# main-pcb_aveon.net
KiCad netlist of a schematic drawn in EAGLE
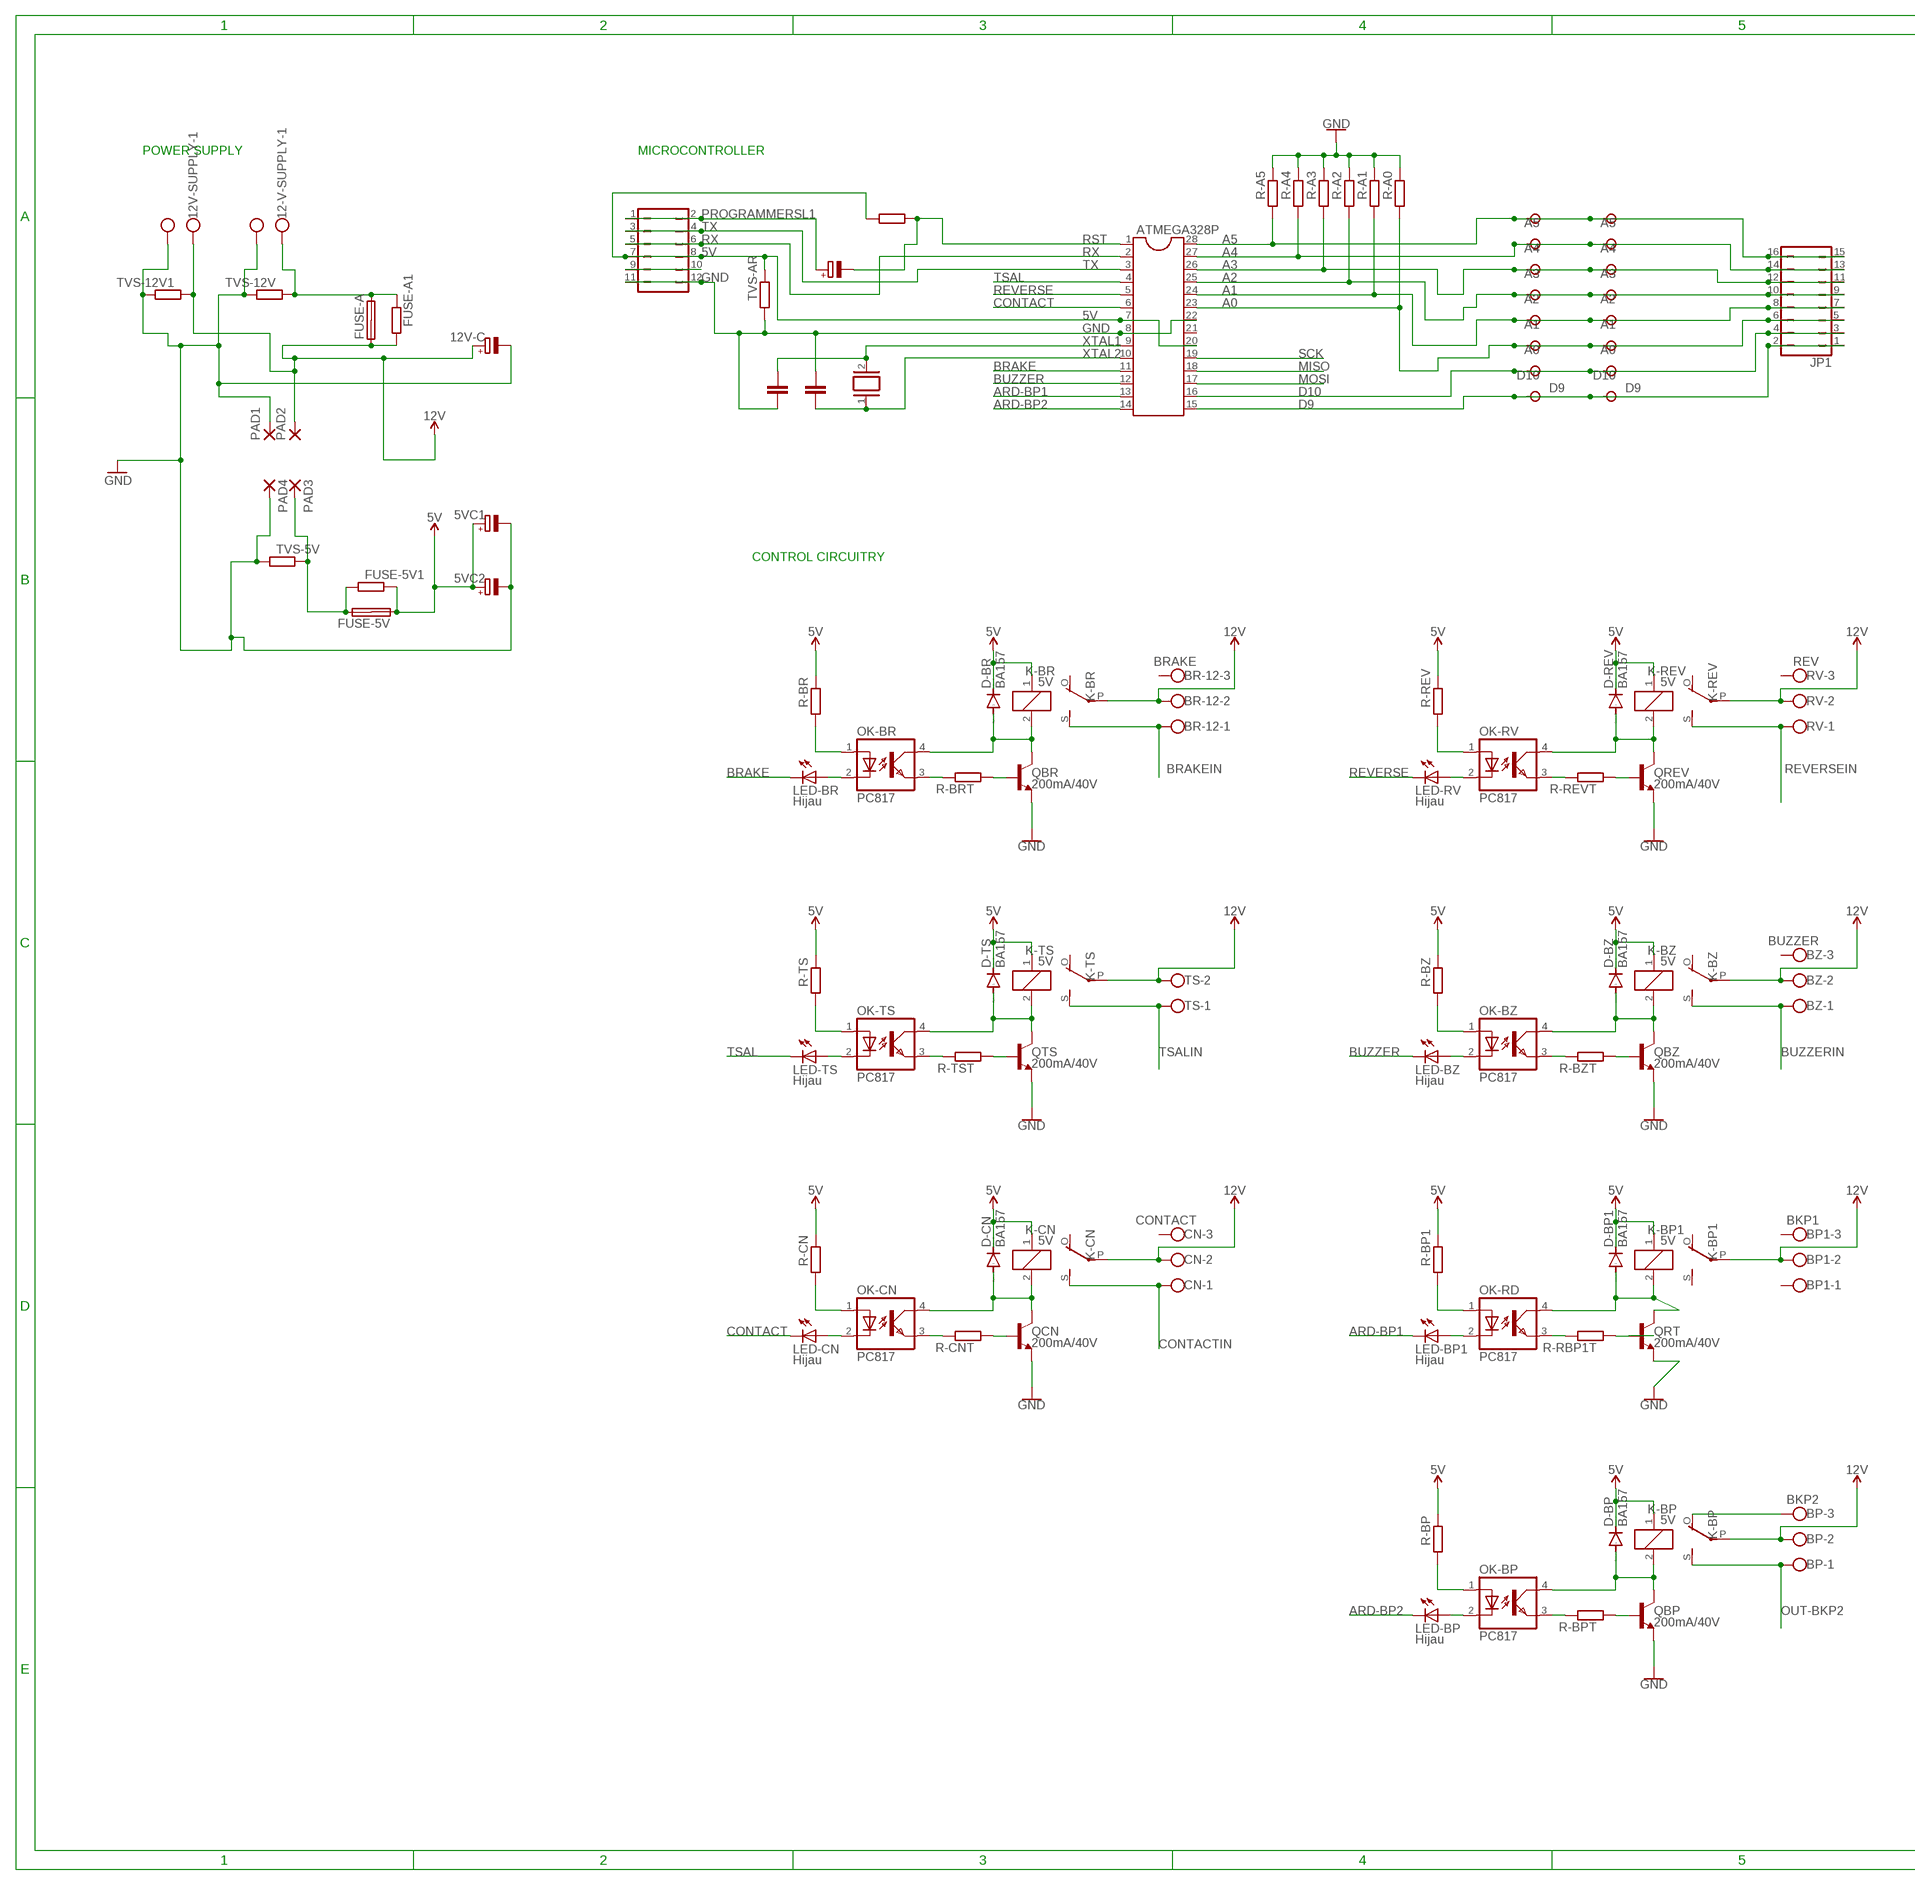
[diagram p0: schematic, sheet 1, part 1 of 2]
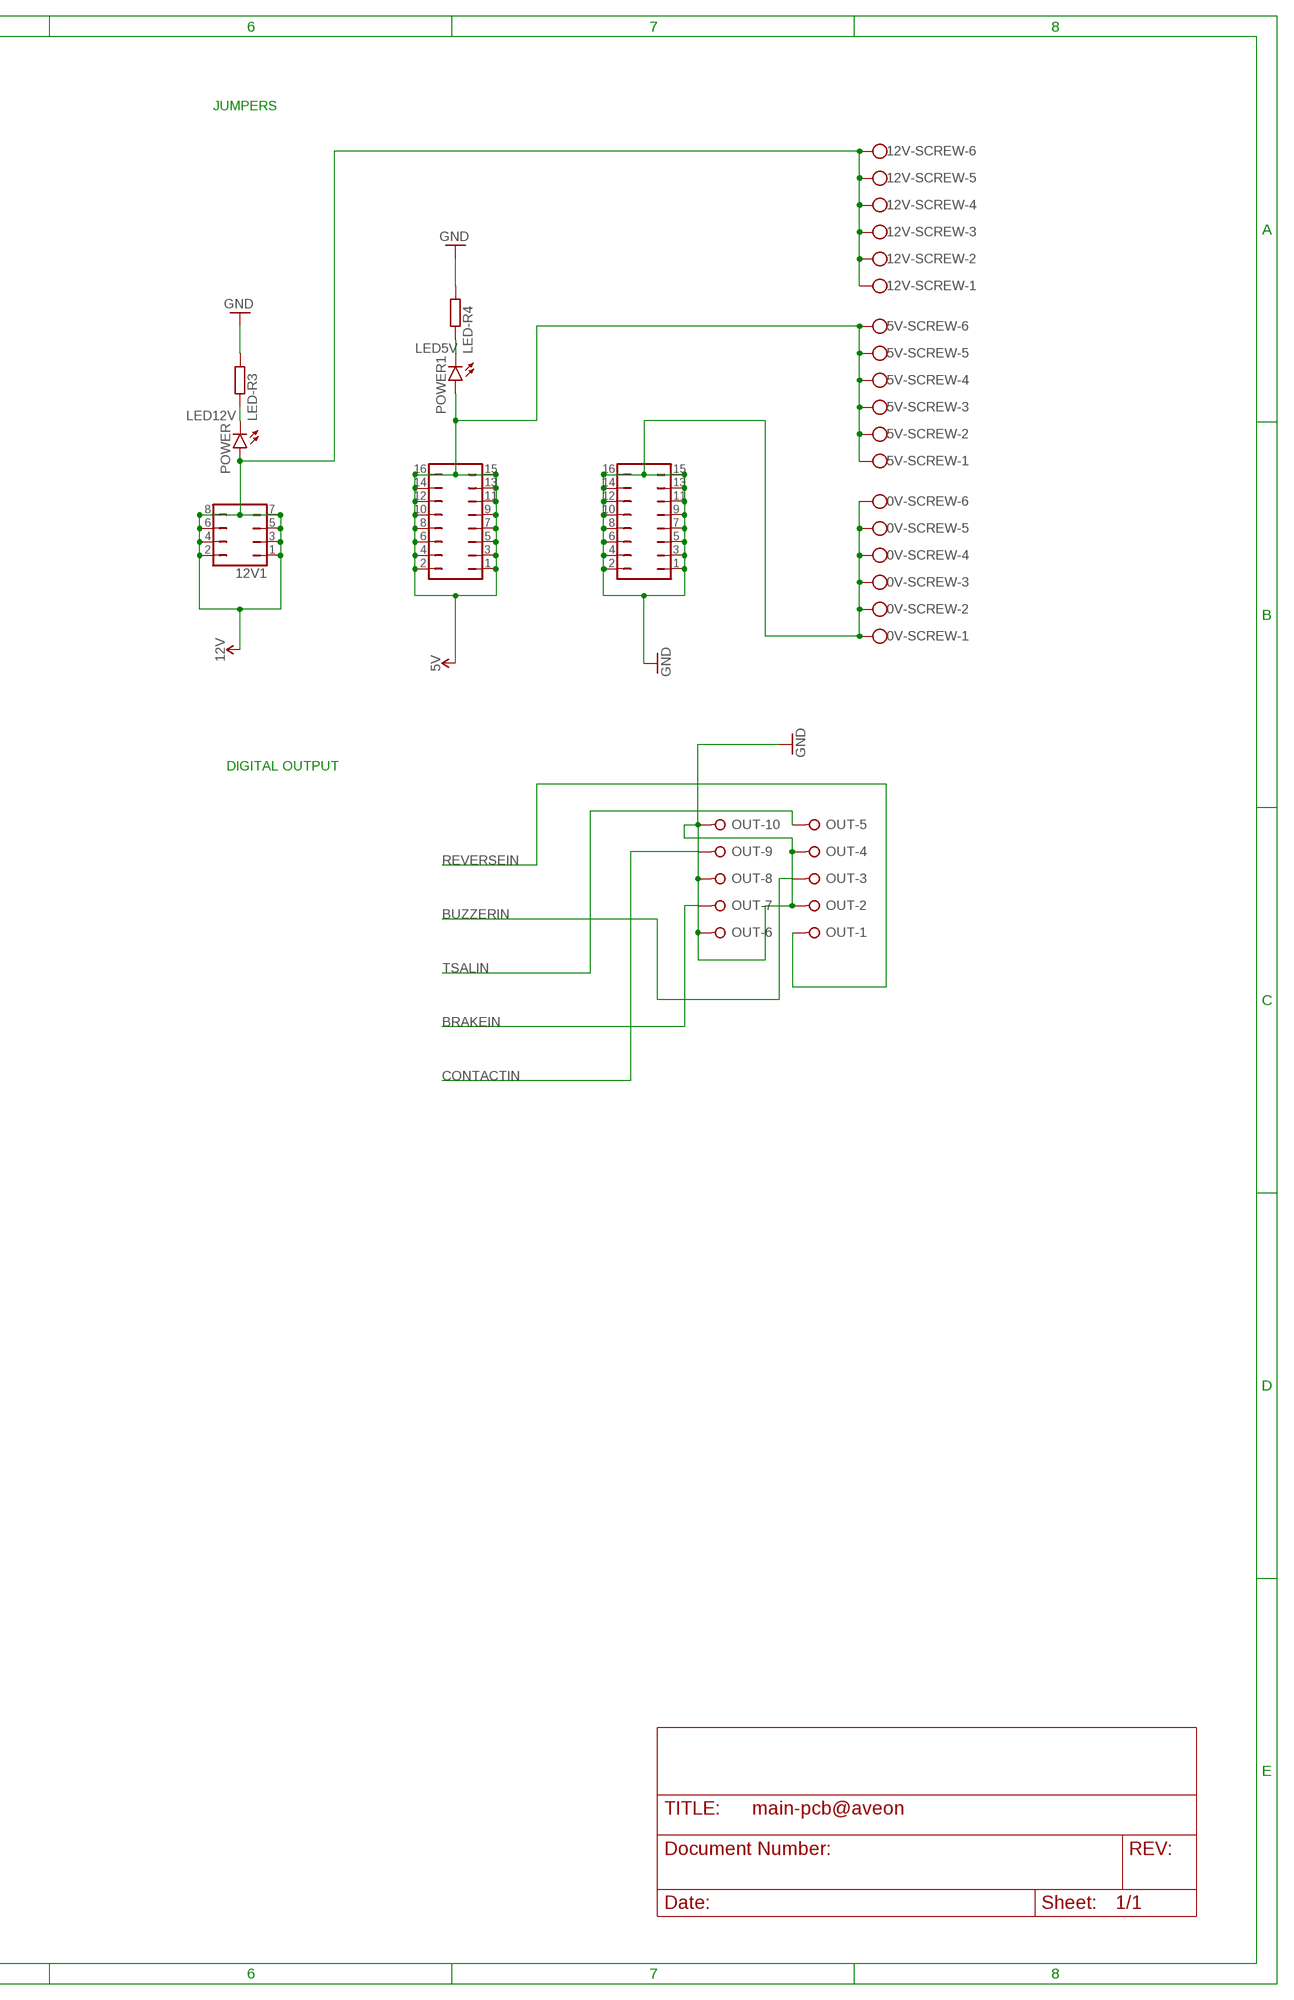
[diagram p1: schematic, sheet 1, part 2 of 2]

(export (version "E")
  (design (tool "Eeschema 10.0.6"))
  (components
    (comp (ref "0V-SCREW")
      (value "W237-6")
      (footprint "eagle-import:W237-6")
      (libsource (lib "eagle-import") (part "W237-6"))
    )
    (comp (ref "5V")
      (value "JP8Q")
      (footprint "eagle-import:JP8Q")
      (libsource (lib "eagle-import") (part "JP8Q"))
    )
    (comp (ref "5V-SCREW")
      (value "W237-6")
      (footprint "eagle-import:W237-6")
      (libsource (lib "eagle-import") (part "W237-6"))
    )
    (comp (ref "5V1")
      (value "JP8Q")
      (footprint "eagle-import:JP8Q")
      (libsource (lib "eagle-import") (part "JP8Q"))
    )
    (comp (ref "5VC-2")
      (value "CPOL-EUE5-10.5")
      (footprint "eagle-import:E5-10,5")
      (libsource (lib "eagle-import") (part "CPOL-EUE5-10.5"))
    )
    (comp (ref "5VC1")
      (value "CPOL-EUE5-10.5")
      (footprint "eagle-import:E5-10,5")
      (libsource (lib "eagle-import") (part "CPOL-EUE5-10.5"))
    )
    (comp (ref "12-V-SUPPLY")
      (value "W237-102")
      (footprint "eagle-import:W237-102")
      (fields (field (name "MPN") "237-102"))
      (libsource (lib "eagle-import") (part "W237-102"))
    )
    (comp (ref "12V-C")
      (value "CPOL-EUE5-10.5")
      (footprint "eagle-import:E5-10,5")
      (libsource (lib "eagle-import") (part "CPOL-EUE5-10.5"))
    )
    (comp (ref "12V-SCREW")
      (value "W237-6")
      (footprint "eagle-import:W237-6")
      (libsource (lib "eagle-import") (part "W237-6"))
    )
    (comp (ref "12V-SUPPLY")
      (value "W237-102")
      (footprint "eagle-import:W237-102")
      (fields (field (name "MPN") "237-102"))
      (libsource (lib "eagle-import") (part "W237-102"))
    )
    (comp (ref "12V1")
      (value "JP4Q")
      (footprint "eagle-import:JP4Q")
      (libsource (lib "eagle-import") (part "JP4Q"))
    )
    (comp (ref "A-1")
      (value "W237-08P")
      (footprint "eagle-import:W237-8P")
      (fields (field (name "A0") "123"))
      (libsource (lib "eagle-import") (part "W237-08P"))
    )
    (comp (ref "A-2")
      (value "W237-08P")
      (footprint "eagle-import:W237-8P")
      (libsource (lib "eagle-import") (part "W237-08P"))
    )
    (comp (ref "ATMEGA328P")
      (value "DIL28-3")
      (footprint "eagle-import:DIL28-3")
      (libsource (lib "eagle-import") (part "DIL28-3"))
    )
    (comp (ref "BP")
      (value "BKP2")
      (footprint "eagle-import:W237-103")
      (fields (field (name "MPN") "237-103"))
      (libsource (lib "eagle-import") (part "W237-103"))
    )
    (comp (ref "BP1")
      (value "BKP1")
      (footprint "eagle-import:W237-103")
      (fields (field (name "MPN") "237-103"))
      (libsource (lib "eagle-import") (part "W237-103"))
    )
    (comp (ref "BR-12")
      (value "BRAKE")
      (footprint "eagle-import:W237-103")
      (fields (field (name "MPN") "237-103"))
      (libsource (lib "eagle-import") (part "W237-103"))
    )
    (comp (ref "BZ")
      (value "BUZZER")
      (footprint "eagle-import:W237-103")
      (fields (field (name "MPN") "237-103"))
      (libsource (lib "eagle-import") (part "W237-103"))
    )
    (comp (ref "C1")
      (value "C-EU025-030X050")
      (footprint "eagle-import:C025-030X050")
      (libsource (lib "eagle-import") (part "C-EU025-030X050"))
    )
    (comp (ref "C2")
      (value "C-EU025-030X050")
      (footprint "eagle-import:C025-030X050")
      (libsource (lib "eagle-import") (part "C-EU025-030X050"))
    )
    (comp (ref "CN")
      (value "CONTACT")
      (footprint "eagle-import:W237-103")
      (fields (field (name "MPN") "237-103"))
      (libsource (lib "eagle-import") (part "W237-103"))
    )
    (comp (ref "CRYSTAL")
      (value "XTAL/S")
      (footprint "eagle-import:QS")
      (libsource (lib "eagle-import") (part "XTAL/S"))
    )
    (comp (ref "D-BP")
      (value "BA157")
      (footprint "eagle-import:P1-10")
      (libsource (lib "eagle-import") (part "BA157"))
    )
    (comp (ref "D-BP1")
      (value "BA157")
      (footprint "eagle-import:P1-10")
      (libsource (lib "eagle-import") (part "BA157"))
    )
    (comp (ref "D-BR")
      (value "BA157")
      (footprint "eagle-import:P1-10")
      (libsource (lib "eagle-import") (part "BA157"))
    )
    (comp (ref "D-BZ")
      (value "BA157")
      (footprint "eagle-import:P1-10")
      (libsource (lib "eagle-import") (part "BA157"))
    )
    (comp (ref "D-CN")
      (value "BA157")
      (footprint "eagle-import:P1-10")
      (libsource (lib "eagle-import") (part "BA157"))
    )
    (comp (ref "D-REV")
      (value "BA157")
      (footprint "eagle-import:P1-10")
      (libsource (lib "eagle-import") (part "BA157"))
    )
    (comp (ref "D-TS")
      (value "BA157")
      (footprint "eagle-import:P1-10")
      (libsource (lib "eagle-import") (part "BA157"))
    )
    (comp (ref "FUSE-5V")
      (value "SHK20L")
      (footprint "eagle-import:SHK20L")
      (libsource (lib "eagle-import") (part "SHK20L"))
    )
    (comp (ref "FUSE-5V1")
      (value "R-EU_0204/7")
      (footprint "eagle-import:0204_7")
      (libsource (lib "eagle-import") (part "R-EU_0204/7"))
    )
    (comp (ref "FUSE-A")
      (value "SHK20L")
      (footprint "eagle-import:SHK20L")
      (libsource (lib "eagle-import") (part "SHK20L"))
    )
    (comp (ref "FUSE-A1")
      (value "R-EU_0204/7")
      (footprint "eagle-import:0204_7")
      (libsource (lib "eagle-import") (part "R-EU_0204/7"))
    )
    (comp (ref "JP1")
      (value "JP8Q")
      (footprint "eagle-import:JP8Q")
      (libsource (lib "eagle-import") (part "JP8Q"))
    )
    (comp (ref "K-BP")
      (value "5V")
      (footprint "eagle-import:ZF112")
      (libsource (lib "eagle-import") (part "ZF112"))
    )
    (comp (ref "K-BP1")
      (value "5V")
      (footprint "eagle-import:ZF112")
      (libsource (lib "eagle-import") (part "ZF112"))
    )
    (comp (ref "K-BR")
      (value "5V")
      (footprint "eagle-import:ZF112")
      (libsource (lib "eagle-import") (part "ZF112"))
    )
    (comp (ref "K-BZ")
      (value "5V")
      (footprint "eagle-import:ZF112")
      (libsource (lib "eagle-import") (part "ZF112"))
    )
    (comp (ref "K-CN")
      (value "5V")
      (footprint "eagle-import:ZF112")
      (libsource (lib "eagle-import") (part "ZF112"))
    )
    (comp (ref "K-REV")
      (value "5V")
      (footprint "eagle-import:ZF112")
      (libsource (lib "eagle-import") (part "ZF112"))
    )
    (comp (ref "K-TS")
      (value "5V")
      (footprint "eagle-import:ZF112")
      (libsource (lib "eagle-import") (part "ZF112"))
    )
    (comp (ref "LED-BP")
      (value "Hijau")
      (footprint "eagle-import:LED3MM")
      (libsource (lib "eagle-import") (part "LED3MM"))
    )
    (comp (ref "LED-BP1")
      (value "Hijau")
      (footprint "eagle-import:LED3MM")
      (libsource (lib "eagle-import") (part "LED3MM"))
    )
    (comp (ref "LED-BR")
      (value "Hijau")
      (footprint "eagle-import:LED3MM")
      (libsource (lib "eagle-import") (part "LED3MM"))
    )
    (comp (ref "LED-BZ")
      (value "Hijau")
      (footprint "eagle-import:LED3MM")
      (libsource (lib "eagle-import") (part "LED3MM"))
    )
    (comp (ref "LED-CN")
      (value "Hijau")
      (footprint "eagle-import:LED3MM")
      (libsource (lib "eagle-import") (part "LED3MM"))
    )
    (comp (ref "LED-R3")
      (value "R-EU_0204/7")
      (footprint "eagle-import:0204_7")
      (libsource (lib "eagle-import") (part "R-EU_0204/7"))
    )
    (comp (ref "LED-R4")
      (value "R-EU_0204/7")
      (footprint "eagle-import:0204_7")
      (libsource (lib "eagle-import") (part "R-EU_0204/7"))
    )
    (comp (ref "LED-RV")
      (value "Hijau")
      (footprint "eagle-import:LED3MM")
      (libsource (lib "eagle-import") (part "LED3MM"))
    )
    (comp (ref "LED-TS")
      (value "Hijau")
      (footprint "eagle-import:LED3MM")
      (libsource (lib "eagle-import") (part "LED3MM"))
    )
    (comp (ref "OK-BP")
      (value "PC817")
      (footprint "eagle-import:DIL04")
      (fields (field (name "MPN") "PC817X4J000F"))
      (libsource (lib "eagle-import") (part "PC817"))
    )
    (comp (ref "OK-BR")
      (value "PC817")
      (footprint "eagle-import:DIL04")
      (fields (field (name "MPN") "PC817X4J000F"))
      (libsource (lib "eagle-import") (part "PC817"))
    )
    (comp (ref "OK-BZ")
      (value "PC817")
      (footprint "eagle-import:DIL04")
      (fields (field (name "MPN") "PC817X4J000F"))
      (libsource (lib "eagle-import") (part "PC817"))
    )
    (comp (ref "OK-CN")
      (value "PC817")
      (footprint "eagle-import:DIL04")
      (fields (field (name "MPN") "PC817X4J000F"))
      (libsource (lib "eagle-import") (part "PC817"))
    )
    (comp (ref "OK-RD")
      (value "PC817")
      (footprint "eagle-import:DIL04")
      (fields (field (name "MPN") "PC817X4J000F"))
      (libsource (lib "eagle-import") (part "PC817"))
    )
    (comp (ref "OK-RV")
      (value "PC817")
      (footprint "eagle-import:DIL04")
      (fields (field (name "MPN") "PC817X4J000F"))
      (libsource (lib "eagle-import") (part "PC817"))
    )
    (comp (ref "OK-TS")
      (value "PC817")
      (footprint "eagle-import:DIL04")
      (fields (field (name "MPN") "PC817X4J000F"))
      (libsource (lib "eagle-import") (part "PC817"))
    )
    (comp (ref "OUT")
      (value "W237-10P")
      (footprint "eagle-import:W237-10P")
      (libsource (lib "eagle-import") (part "W237-10P"))
    )
    (comp (ref "PAD1")
      (value "2,54/1,1")
      (footprint "eagle-import:2,54_1,1")
      (libsource (lib "eagle-import") (part "2,54/1,1"))
    )
    (comp (ref "PAD2")
      (value "2,54/1,1")
      (footprint "eagle-import:2,54_1,1")
      (libsource (lib "eagle-import") (part "2,54/1,1"))
    )
    (comp (ref "PAD3")
      (value "2,54/1,1")
      (footprint "eagle-import:2,54_1,1")
      (libsource (lib "eagle-import") (part "2,54/1,1"))
    )
    (comp (ref "PAD4")
      (value "2,54/1,1")
      (footprint "eagle-import:2,54_1,1")
      (libsource (lib "eagle-import") (part "2,54/1,1"))
    )
    (comp (ref "POWER")
      (value "LED5MM")
      (footprint "eagle-import:LED5MM")
      (libsource (lib "eagle-import") (part "led_259_LED5MM"))
    )
    (comp (ref "POWER1")
      (value "LED5MM")
      (footprint "eagle-import:LED5MM")
      (libsource (lib "eagle-import") (part "led_259_LED5MM"))
    )
    (comp (ref "PROGRAMMER")
      (value "JP6Q")
      (footprint "eagle-import:JP6Q")
      (libsource (lib "eagle-import") (part "JP6Q"))
    )
    (comp (ref "QBP")
      (value "200mA/40V")
      (footprint "eagle-import:TO-92")
      (libsource (lib "eagle-import") (part "TRANS_NPN-2N3904"))
    )
    (comp (ref "QBR")
      (value "200mA/40V")
      (footprint "eagle-import:TO-92")
      (libsource (lib "eagle-import") (part "TRANS_NPN-2N3904"))
    )
    (comp (ref "QBZ")
      (value "200mA/40V")
      (footprint "eagle-import:TO-92")
      (libsource (lib "eagle-import") (part "TRANS_NPN-2N3904"))
    )
    (comp (ref "QCN")
      (value "200mA/40V")
      (footprint "eagle-import:TO-92")
      (libsource (lib "eagle-import") (part "TRANS_NPN-2N3904"))
    )
    (comp (ref "QREV")
      (value "200mA/40V")
      (footprint "eagle-import:TO-92")
      (libsource (lib "eagle-import") (part "TRANS_NPN-2N3904"))
    )
    (comp (ref "QRT")
      (value "200mA/40V")
      (footprint "eagle-import:TO-92")
      (libsource (lib "eagle-import") (part "TRANS_NPN-2N3904"))
    )
    (comp (ref "QTS")
      (value "200mA/40V")
      (footprint "eagle-import:TO-92")
      (libsource (lib "eagle-import") (part "TRANS_NPN-2N3904"))
    )
    (comp (ref "R-A0")
      (value "R-EU_0204/7")
      (footprint "eagle-import:0204_7")
      (libsource (lib "eagle-import") (part "R-EU_0204/7"))
    )
    (comp (ref "R-A1")
      (value "R-EU_0204/7")
      (footprint "eagle-import:0204_7")
      (libsource (lib "eagle-import") (part "R-EU_0204/7"))
    )
    (comp (ref "R-A2")
      (value "R-EU_0204/7")
      (footprint "eagle-import:0204_7")
      (libsource (lib "eagle-import") (part "R-EU_0204/7"))
    )
    (comp (ref "R-A3")
      (value "R-EU_0204/7")
      (footprint "eagle-import:0204_7")
      (libsource (lib "eagle-import") (part "R-EU_0204/7"))
    )
    (comp (ref "R-A4")
      (value "R-EU_0204/7")
      (footprint "eagle-import:0204_7")
      (libsource (lib "eagle-import") (part "R-EU_0204/7"))
    )
    (comp (ref "R-A5")
      (value "R-EU_0204/7")
      (footprint "eagle-import:0204_7")
      (libsource (lib "eagle-import") (part "R-EU_0204/7"))
    )
    (comp (ref "R-BP")
      (value "R-EU_0204/7")
      (footprint "eagle-import:0204_7")
      (libsource (lib "eagle-import") (part "R-EU_0204/7"))
    )
    (comp (ref "R-BP1")
      (value "R-EU_0204/7")
      (footprint "eagle-import:0204_7")
      (libsource (lib "eagle-import") (part "R-EU_0204/7"))
    )
    (comp (ref "R-BPT")
      (value "R-EU_0204/7")
      (footprint "eagle-import:0204_7")
      (libsource (lib "eagle-import") (part "R-EU_0204/7"))
    )
    (comp (ref "R-BR")
      (value "R-EU_0204/7")
      (footprint "eagle-import:0204_7")
      (libsource (lib "eagle-import") (part "R-EU_0204/7"))
    )
    (comp (ref "R-BRT")
      (value "R-EU_0204/7")
      (footprint "eagle-import:0204_7")
      (libsource (lib "eagle-import") (part "R-EU_0204/7"))
    )
    (comp (ref "R-BZ")
      (value "R-EU_0204/7")
      (footprint "eagle-import:0204_7")
      (libsource (lib "eagle-import") (part "R-EU_0204/7"))
    )
    (comp (ref "R-BZT")
      (value "R-EU_0204/7")
      (footprint "eagle-import:0204_7")
      (libsource (lib "eagle-import") (part "R-EU_0204/7"))
    )
    (comp (ref "R-CN")
      (value "R-EU_0204/7")
      (footprint "eagle-import:0204_7")
      (libsource (lib "eagle-import") (part "R-EU_0204/7"))
    )
    (comp (ref "R-CNT")
      (value "R-EU_0204/7")
      (footprint "eagle-import:0204_7")
      (libsource (lib "eagle-import") (part "R-EU_0204/7"))
    )
    (comp (ref "R-RBP1T")
      (value "R-EU_0204/7")
      (footprint "eagle-import:0204_7")
      (libsource (lib "eagle-import") (part "R-EU_0204/7"))
    )
    (comp (ref "R-REV")
      (value "R-EU_0204/7")
      (footprint "eagle-import:0204_7")
      (libsource (lib "eagle-import") (part "R-EU_0204/7"))
    )
    (comp (ref "R-REVT")
      (value "R-EU_0204/7")
      (footprint "eagle-import:0204_7")
      (libsource (lib "eagle-import") (part "R-EU_0204/7"))
    )
    (comp (ref "R-TS")
      (value "R-EU_0204/7")
      (footprint "eagle-import:0204_7")
      (libsource (lib "eagle-import") (part "R-EU_0204/7"))
    )
    (comp (ref "R-TST")
      (value "R-EU_0204/7")
      (footprint "eagle-import:0204_7")
      (libsource (lib "eagle-import") (part "R-EU_0204/7"))
    )
    (comp (ref "RST-C")
      (value "CPOL-EUE2.5-6")
      (footprint "eagle-import:E2,5-6")
      (libsource (lib "eagle-import") (part "CPOL-EUE2.5-6"))
    )
    (comp (ref "RST-R")
      (value "R-EU_0204/7")
      (footprint "eagle-import:0204_7")
      (libsource (lib "eagle-import") (part "R-EU_0204/7"))
    )
    (comp (ref "RV")
      (value "REV")
      (footprint "eagle-import:W237-103")
      (fields (field (name "MPN") "237-103"))
      (libsource (lib "eagle-import") (part "W237-103"))
    )
    (comp (ref "TS")
      (value "TSAL")
      (footprint "eagle-import:W237-103")
      (fields (field (name "MPN") "237-103"))
      (libsource (lib "eagle-import") (part "W237-103"))
    )
    (comp (ref "TVS-5V")
      (value "R-EU_0204/7")
      (footprint "eagle-import:0204_7")
      (libsource (lib "eagle-import") (part "R-EU_0204/7"))
    )
    (comp (ref "TVS-12V")
      (value "R-EU_0204/7")
      (footprint "eagle-import:0204_7")
      (libsource (lib "eagle-import") (part "R-EU_0204/7"))
    )
    (comp (ref "TVS-12V1")
      (value "R-EU_0204/7")
      (footprint "eagle-import:0204_7")
      (libsource (lib "eagle-import") (part "R-EU_0204/7"))
    )
    (comp (ref "TVS-AR")
      (value "R-EU_0204/7")
      (footprint "eagle-import:0204_7")
      (libsource (lib "eagle-import") (part "R-EU_0204/7"))
    )
  )
  (nets
    (net (code "1") (name "/A0") (class "Default")
      (node (ref "A-1") (pin "3") (pinfunction "KL_3") (pintype "passive"))
      (node (ref "A-2") (pin "3") (pinfunction "KL_3") (pintype "passive"))
      (node (ref "ATMEGA328P") (pin "23") (pinfunction "23_23") (pintype "passive"))
      (node (ref "JP1") (pin "5") (pinfunction "5_5") (pintype "passive"))
      (node (ref "JP1") (pin "6") (pinfunction "6_6") (pintype "passive"))
      (node (ref "R-A0") (pin "1") (pinfunction "1_1") (pintype "passive"))
    )
    (net (code "2") (name "/A1") (class "Default")
      (node (ref "A-1") (pin "4") (pinfunction "KL_4") (pintype "passive"))
      (node (ref "A-2") (pin "4") (pinfunction "KL_4") (pintype "passive"))
      (node (ref "ATMEGA328P") (pin "24") (pinfunction "24_24") (pintype "passive"))
      (node (ref "JP1") (pin "7") (pinfunction "7_7") (pintype "passive"))
      (node (ref "JP1") (pin "8") (pinfunction "8_8") (pintype "passive"))
      (node (ref "R-A1") (pin "1") (pinfunction "1_1") (pintype "passive"))
    )
    (net (code "3") (name "/A2") (class "Default")
      (node (ref "A-1") (pin "5") (pinfunction "KL_5") (pintype "passive"))
      (node (ref "A-2") (pin "5") (pinfunction "KL_5") (pintype "passive"))
      (node (ref "ATMEGA328P") (pin "25") (pinfunction "25_25") (pintype "passive"))
      (node (ref "JP1") (pin "10") (pinfunction "10_10") (pintype "passive"))
      (node (ref "JP1") (pin "9") (pinfunction "9_9") (pintype "passive"))
      (node (ref "R-A2") (pin "1") (pinfunction "1_1") (pintype "passive"))
    )
    (net (code "4") (name "/A3") (class "Default")
      (node (ref "A-1") (pin "6") (pinfunction "KL_6") (pintype "passive"))
      (node (ref "A-2") (pin "6") (pinfunction "KL_6") (pintype "passive"))
      (node (ref "ATMEGA328P") (pin "26") (pinfunction "26_26") (pintype "passive"))
      (node (ref "JP1") (pin "11") (pinfunction "11_11") (pintype "passive"))
      (node (ref "JP1") (pin "12") (pinfunction "12_12") (pintype "passive"))
      (node (ref "R-A3") (pin "1") (pinfunction "1_1") (pintype "passive"))
    )
    (net (code "5") (name "/A4") (class "Default")
      (node (ref "A-1") (pin "7") (pinfunction "KL_7") (pintype "passive"))
      (node (ref "A-2") (pin "7") (pinfunction "KL_7") (pintype "passive"))
      (node (ref "ATMEGA328P") (pin "27") (pinfunction "27_27") (pintype "passive"))
      (node (ref "JP1") (pin "13") (pinfunction "13_13") (pintype "passive"))
      (node (ref "JP1") (pin "14") (pinfunction "14_14") (pintype "passive"))
      (node (ref "R-A4") (pin "1") (pinfunction "1_1") (pintype "passive"))
    )
    (net (code "6") (name "/A5") (class "Default")
      (node (ref "A-1") (pin "8") (pinfunction "KL_8") (pintype "passive"))
      (node (ref "A-2") (pin "8") (pinfunction "KL_8") (pintype "passive"))
      (node (ref "ATMEGA328P") (pin "28") (pinfunction "28_28") (pintype "passive"))
      (node (ref "JP1") (pin "15") (pinfunction "15_15") (pintype "passive"))
      (node (ref "JP1") (pin "16") (pinfunction "16_16") (pintype "passive"))
      (node (ref "R-A5") (pin "1") (pinfunction "1_1") (pintype "passive"))
    )
    (net (code "7") (name "/ARD-BP1") (class "Default")
      (node (ref "ATMEGA328P") (pin "13") (pinfunction "13_13") (pintype "passive"))
      (node (ref "LED-BP1") (pin "K") (pinfunction "C_K") (pintype "passive"))
    )
    (net (code "8") (name "/ARD-BP2") (class "Default")
      (node (ref "ATMEGA328P") (pin "14") (pinfunction "14_14") (pintype "passive"))
      (node (ref "LED-BP") (pin "K") (pinfunction "C_K") (pintype "passive"))
    )
    (net (code "9") (name "/BRAKE") (class "Default")
      (node (ref "ATMEGA328P") (pin "11") (pinfunction "11_11") (pintype "passive"))
      (node (ref "LED-BR") (pin "K") (pinfunction "C_K") (pintype "passive"))
    )
    (net (code "10") (name "/BRAKEIN") (class "Default")
      (node (ref "BR-12") (pin "1") (pinfunction "KL_1") (pintype "passive"))
      (node (ref "K-BR") (pin "S") (pinfunction "S_S") (pintype "passive"))
      (node (ref "OUT") (pin "7") (pinfunction "KL_7") (pintype "passive"))
    )
    (net (code "11") (name "/BUZZER") (class "Default")
      (node (ref "ATMEGA328P") (pin "12") (pinfunction "12_12") (pintype "passive"))
      (node (ref "LED-BZ") (pin "K") (pinfunction "C_K") (pintype "passive"))
    )
    (net (code "12") (name "/BUZZERIN") (class "Default")
      (node (ref "BZ") (pin "1") (pinfunction "KL_1") (pintype "passive"))
      (node (ref "K-BZ") (pin "S") (pinfunction "S_S") (pintype "passive"))
      (node (ref "OUT") (pin "3") (pinfunction "KL_3") (pintype "passive"))
    )
    (net (code "13") (name "/CONTACT") (class "Default")
      (node (ref "ATMEGA328P") (pin "6") (pinfunction "6_6") (pintype "passive"))
      (node (ref "LED-CN") (pin "K") (pinfunction "C_K") (pintype "passive"))
    )
    (net (code "14") (name "/CONTACTIN") (class "Default")
      (node (ref "CN") (pin "1") (pinfunction "KL_1") (pintype "passive"))
      (node (ref "K-CN") (pin "S") (pinfunction "S_S") (pintype "passive"))
      (node (ref "OUT") (pin "9") (pinfunction "KL_9") (pintype "passive"))
    )
    (net (code "15") (name "/D9") (class "Default")
      (node (ref "A-1") (pin "1") (pinfunction "KL_1") (pintype "passive"))
      (node (ref "A-2") (pin "1") (pinfunction "KL_1") (pintype "passive"))
      (node (ref "ATMEGA328P") (pin "15") (pinfunction "15_15") (pintype "passive"))
      (node (ref "JP1") (pin "1") (pinfunction "1_1") (pintype "passive"))
      (node (ref "JP1") (pin "2") (pinfunction "2_2") (pintype "passive"))
    )
    (net (code "16") (name "/D10") (class "Default")
      (node (ref "A-1") (pin "2") (pinfunction "KL_2") (pintype "passive"))
      (node (ref "A-2") (pin "2") (pinfunction "KL_2") (pintype "passive"))
      (node (ref "ATMEGA328P") (pin "16") (pinfunction "16_16") (pintype "passive"))
      (node (ref "JP1") (pin "3") (pinfunction "3_3") (pintype "passive"))
      (node (ref "JP1") (pin "4") (pinfunction "4_4") (pintype "passive"))
    )
    (net (code "17") (name "/LED5V") (class "Default")
      (node (ref "LED-R4") (pin "2") (pinfunction "2_2") (pintype "passive"))
      (node (ref "POWER1") (pin "K") (pinfunction "C_K") (pintype "passive"))
    )
    (net (code "18") (name "/LED12V") (class "Default")
      (node (ref "LED-R3") (pin "2") (pinfunction "2_2") (pintype "passive"))
      (node (ref "POWER") (pin "K") (pinfunction "C_K") (pintype "passive"))
    )
    (net (code "19") (name "/MISO") (class "Default")
      (node (ref "ATMEGA328P") (pin "18") (pinfunction "18_18") (pintype "passive"))
    )
    (net (code "20") (name "/MOSI") (class "Default")
      (node (ref "ATMEGA328P") (pin "17") (pinfunction "17_17") (pintype "passive"))
    )
    (net (code "21") (name "/OUT-BKP2") (class "Default")
      (node (ref "BP") (pin "1") (pinfunction "KL_1") (pintype "passive"))
      (node (ref "K-BP") (pin "S") (pinfunction "S_S") (pintype "passive"))
    )
    (net (code "22") (name "/PROGRAMMERSL1") (class "Default")
      (node (ref "PROGRAMMER") (pin "1") (pinfunction "1_1") (pintype "passive"))
      (node (ref "PROGRAMMER") (pin "2") (pinfunction "2_2") (pintype "passive"))
      (node (ref "RST-C") (pin "+") (pinfunction "+_+") (pintype "passive"))
    )
    (net (code "23") (name "/REVERSE") (class "Default")
      (node (ref "ATMEGA328P") (pin "5") (pinfunction "5_5") (pintype "passive"))
      (node (ref "LED-RV") (pin "K") (pinfunction "C_K") (pintype "passive"))
    )
    (net (code "24") (name "/REVERSEIN") (class "Default")
      (node (ref "K-REV") (pin "S") (pinfunction "S_S") (pintype "passive"))
      (node (ref "OUT") (pin "1") (pinfunction "KL_1") (pintype "passive"))
      (node (ref "RV") (pin "1") (pinfunction "KL_1") (pintype "passive"))
    )
    (net (code "25") (name "/RST") (class "Default")
      (node (ref "ATMEGA328P") (pin "1") (pinfunction "1_1") (pintype "passive"))
      (node (ref "RST-C") (pin "-") (pinfunction "-_-") (pintype "passive"))
      (node (ref "RST-R") (pin "2") (pinfunction "2_2") (pintype "passive"))
    )
    (net (code "26") (name "/RX") (class "Default")
      (node (ref "ATMEGA328P") (pin "2") (pinfunction "2_2") (pintype "passive"))
      (node (ref "PROGRAMMER") (pin "5") (pinfunction "5_5") (pintype "passive"))
      (node (ref "PROGRAMMER") (pin "6") (pinfunction "6_6") (pintype "passive"))
    )
    (net (code "27") (name "/SCK") (class "Default")
      (node (ref "ATMEGA328P") (pin "19") (pinfunction "19_19") (pintype "passive"))
    )
    (net (code "28") (name "/TSAL") (class "Default")
      (node (ref "ATMEGA328P") (pin "4") (pinfunction "4_4") (pintype "passive"))
      (node (ref "LED-TS") (pin "K") (pinfunction "C_K") (pintype "passive"))
    )
    (net (code "29") (name "/TSALIN") (class "Default")
      (node (ref "K-TS") (pin "S") (pinfunction "S_S") (pintype "passive"))
      (node (ref "OUT") (pin "5") (pinfunction "KL_5") (pintype "passive"))
      (node (ref "TS") (pin "1") (pinfunction "KL_1") (pintype "passive"))
    )
    (net (code "30") (name "/TX") (class "Default")
      (node (ref "ATMEGA328P") (pin "3") (pinfunction "3_3") (pintype "passive"))
      (node (ref "PROGRAMMER") (pin "3") (pinfunction "3_3") (pintype "passive"))
      (node (ref "PROGRAMMER") (pin "4") (pinfunction "4_4") (pintype "passive"))
    )
    (net (code "31") (name "/XTAL1") (class "Default")
      (node (ref "ATMEGA328P") (pin "9") (pinfunction "9_9") (pintype "passive"))
      (node (ref "C1") (pin "2") (pinfunction "2_2") (pintype "passive"))
      (node (ref "CRYSTAL") (pin "2") (pinfunction "2_2") (pintype "passive"))
    )
    (net (code "32") (name "/XTAL2") (class "Default")
      (node (ref "ATMEGA328P") (pin "10") (pinfunction "10_10") (pintype "passive"))
      (node (ref "C2") (pin "1") (pinfunction "1_1") (pintype "passive"))
      (node (ref "CRYSTAL") (pin "1") (pinfunction "1_1") (pintype "passive"))
    )
    (net (code "33") (name "5V") (class "Default")
      (node (ref "5V") (pin "1") (pinfunction "1_1") (pintype "passive"))
      (node (ref "5V") (pin "10") (pinfunction "10_10") (pintype "passive"))
      (node (ref "5V") (pin "11") (pinfunction "11_11") (pintype "passive"))
      (node (ref "5V") (pin "12") (pinfunction "12_12") (pintype "passive"))
      (node (ref "5V") (pin "13") (pinfunction "13_13") (pintype "passive"))
      (node (ref "5V") (pin "14") (pinfunction "14_14") (pintype "passive"))
      (node (ref "5V") (pin "15") (pinfunction "15_15") (pintype "passive"))
      (node (ref "5V") (pin "16") (pinfunction "16_16") (pintype "passive"))
      (node (ref "5V") (pin "2") (pinfunction "2_2") (pintype "passive"))
      (node (ref "5V") (pin "3") (pinfunction "3_3") (pintype "passive"))
      (node (ref "5V") (pin "4") (pinfunction "4_4") (pintype "passive"))
      (node (ref "5V") (pin "5") (pinfunction "5_5") (pintype "passive"))
      (node (ref "5V") (pin "6") (pinfunction "6_6") (pintype "passive"))
      (node (ref "5V") (pin "7") (pinfunction "7_7") (pintype "passive"))
      (node (ref "5V") (pin "8") (pinfunction "8_8") (pintype "passive"))
      (node (ref "5V") (pin "9") (pinfunction "9_9") (pintype "passive"))
      (node (ref "5V-SCREW") (pin "1") (pinfunction "KL_1") (pintype "passive"))
      (node (ref "5V-SCREW") (pin "2") (pinfunction "KL_2") (pintype "passive"))
      (node (ref "5V-SCREW") (pin "3") (pinfunction "KL_3") (pintype "passive"))
      (node (ref "5V-SCREW") (pin "4") (pinfunction "KL_4") (pintype "passive"))
      (node (ref "5V-SCREW") (pin "5") (pinfunction "KL_5") (pintype "passive"))
      (node (ref "5V-SCREW") (pin "6") (pinfunction "KL_6") (pintype "passive"))
      (node (ref "5VC-2") (pin "+") (pinfunction "+_+") (pintype "passive"))
      (node (ref "5VC1") (pin "+") (pinfunction "+_+") (pintype "passive"))
      (node (ref "ATMEGA328P") (pin "20") (pinfunction "20_20") (pintype "passive"))
      (node (ref "ATMEGA328P") (pin "7") (pinfunction "7_7") (pintype "passive"))
      (node (ref "D-BP") (pin "C") (pinfunction "C_C") (pintype "passive"))
      (node (ref "D-BP1") (pin "C") (pinfunction "C_C") (pintype "passive"))
      (node (ref "D-BR") (pin "C") (pinfunction "C_C") (pintype "passive"))
      (node (ref "D-BZ") (pin "C") (pinfunction "C_C") (pintype "passive"))
      (node (ref "D-CN") (pin "C") (pinfunction "C_C") (pintype "passive"))
      (node (ref "D-REV") (pin "C") (pinfunction "C_C") (pintype "passive"))
      (node (ref "D-TS") (pin "C") (pinfunction "C_C") (pintype "passive"))
      (node (ref "FUSE-5V") (pin "1A") (pinfunction "1A_1A") (pintype "passive"))
      (node (ref "FUSE-5V1") (pin "2") (pinfunction "2_2") (pintype "passive"))
      (node (ref "K-BP") (pin "1") (pinfunction "1_1") (pintype "passive"))
      (node (ref "K-BP1") (pin "1") (pinfunction "1_1") (pintype "passive"))
      (node (ref "K-BR") (pin "1") (pinfunction "1_1") (pintype "passive"))
      (node (ref "K-BZ") (pin "1") (pinfunction "1_1") (pintype "passive"))
      (node (ref "K-CN") (pin "1") (pinfunction "1_1") (pintype "passive"))
      (node (ref "K-REV") (pin "1") (pinfunction "1_1") (pintype "passive"))
      (node (ref "K-TS") (pin "1") (pinfunction "1_1") (pintype "passive"))
      (node (ref "POWER1") (pin "A") (pinfunction "A_A") (pintype "passive"))
      (node (ref "PROGRAMMER") (pin "7") (pinfunction "7_7") (pintype "passive"))
      (node (ref "PROGRAMMER") (pin "8") (pinfunction "8_8") (pintype "passive"))
      (node (ref "R-BP") (pin "2") (pinfunction "2_2") (pintype "passive"))
      (node (ref "R-BP1") (pin "2") (pinfunction "2_2") (pintype "passive"))
      (node (ref "R-BR") (pin "2") (pinfunction "2_2") (pintype "passive"))
      (node (ref "R-BZ") (pin "2") (pinfunction "2_2") (pintype "passive"))
      (node (ref "R-CN") (pin "2") (pinfunction "2_2") (pintype "passive"))
      (node (ref "R-REV") (pin "2") (pinfunction "2_2") (pintype "passive"))
      (node (ref "R-TS") (pin "2") (pinfunction "2_2") (pintype "passive"))
      (node (ref "RST-R") (pin "1") (pinfunction "1_1") (pintype "passive"))
      (node (ref "TVS-AR") (pin "2") (pinfunction "2_2") (pintype "passive"))
    )
    (net (code "34") (name "12V") (class "Default")
      (node (ref "12V-C") (pin "+") (pinfunction "+_+") (pintype "passive"))
      (node (ref "12V-SCREW") (pin "1") (pinfunction "KL_1") (pintype "passive"))
      (node (ref "12V-SCREW") (pin "2") (pinfunction "KL_2") (pintype "passive"))
      (node (ref "12V-SCREW") (pin "3") (pinfunction "KL_3") (pintype "passive"))
      (node (ref "12V-SCREW") (pin "4") (pinfunction "KL_4") (pintype "passive"))
      (node (ref "12V-SCREW") (pin "5") (pinfunction "KL_5") (pintype "passive"))
      (node (ref "12V-SCREW") (pin "6") (pinfunction "KL_6") (pintype "passive"))
      (node (ref "12V-SUPPLY") (pin "1") (pinfunction "KL_1") (pintype "passive"))
      (node (ref "12V1") (pin "1") (pinfunction "1_1") (pintype "passive"))
      (node (ref "12V1") (pin "2") (pinfunction "2_2") (pintype "passive"))
      (node (ref "12V1") (pin "3") (pinfunction "3_3") (pintype "passive"))
      (node (ref "12V1") (pin "4") (pinfunction "4_4") (pintype "passive"))
      (node (ref "12V1") (pin "5") (pinfunction "5_5") (pintype "passive"))
      (node (ref "12V1") (pin "6") (pinfunction "6_6") (pintype "passive"))
      (node (ref "12V1") (pin "7") (pinfunction "7_7") (pintype "passive"))
      (node (ref "12V1") (pin "8") (pinfunction "8_8") (pintype "passive"))
      (node (ref "BP") (pin "2") (pinfunction "KL_2") (pintype "passive"))
      (node (ref "BP1") (pin "2") (pinfunction "KL_2") (pintype "passive"))
      (node (ref "BR-12") (pin "2") (pinfunction "KL_2") (pintype "passive"))
      (node (ref "BZ") (pin "2") (pinfunction "KL_2") (pintype "passive"))
      (node (ref "CN") (pin "2") (pinfunction "KL_2") (pintype "passive"))
      (node (ref "FUSE-A") (pin "1A") (pinfunction "1A_1A") (pintype "passive"))
      (node (ref "FUSE-A1") (pin "1") (pinfunction "1_1") (pintype "passive"))
      (node (ref "K-BP") (pin "P") (pinfunction "P_P") (pintype "passive"))
      (node (ref "K-BP1") (pin "P") (pinfunction "P_P") (pintype "passive"))
      (node (ref "K-BR") (pin "P") (pinfunction "P_P") (pintype "passive"))
      (node (ref "K-BZ") (pin "P") (pinfunction "P_P") (pintype "passive"))
      (node (ref "K-CN") (pin "P") (pinfunction "P_P") (pintype "passive"))
      (node (ref "K-REV") (pin "P") (pinfunction "P_P") (pintype "passive"))
      (node (ref "K-TS") (pin "P") (pinfunction "P_P") (pintype "passive"))
      (node (ref "PAD2") (pin "1") (pinfunction "P_1") (pintype "passive"))
      (node (ref "POWER") (pin "A") (pinfunction "A_A") (pintype "passive"))
      (node (ref "RV") (pin "2") (pinfunction "KL_2") (pintype "passive"))
      (node (ref "TS") (pin "2") (pinfunction "KL_2") (pintype "passive"))
      (node (ref "TVS-12V1") (pin "1") (pinfunction "1_1") (pintype "passive"))
    )
    (net (code "35") (name "GND") (class "Default")
      (node (ref "0V-SCREW") (pin "1") (pinfunction "KL_1") (pintype "passive"))
      (node (ref "0V-SCREW") (pin "2") (pinfunction "KL_2") (pintype "passive"))
      (node (ref "0V-SCREW") (pin "3") (pinfunction "KL_3") (pintype "passive"))
      (node (ref "0V-SCREW") (pin "4") (pinfunction "KL_4") (pintype "passive"))
      (node (ref "0V-SCREW") (pin "5") (pinfunction "KL_5") (pintype "passive"))
      (node (ref "0V-SCREW") (pin "6") (pinfunction "KL_6") (pintype "passive"))
      (node (ref "12-V-SUPPLY") (pin "2") (pinfunction "KL_2") (pintype "passive"))
      (node (ref "12V-C") (pin "-") (pinfunction "-_-") (pintype "passive"))
      (node (ref "12V-SUPPLY") (pin "2") (pinfunction "KL_2") (pintype "passive"))
      (node (ref "5V1") (pin "1") (pinfunction "1_1") (pintype "passive"))
      (node (ref "5V1") (pin "10") (pinfunction "10_10") (pintype "passive"))
      (node (ref "5V1") (pin "11") (pinfunction "11_11") (pintype "passive"))
      (node (ref "5V1") (pin "12") (pinfunction "12_12") (pintype "passive"))
      (node (ref "5V1") (pin "13") (pinfunction "13_13") (pintype "passive"))
      (node (ref "5V1") (pin "14") (pinfunction "14_14") (pintype "passive"))
      (node (ref "5V1") (pin "15") (pinfunction "15_15") (pintype "passive"))
      (node (ref "5V1") (pin "16") (pinfunction "16_16") (pintype "passive"))
      (node (ref "5V1") (pin "2") (pinfunction "2_2") (pintype "passive"))
      (node (ref "5V1") (pin "3") (pinfunction "3_3") (pintype "passive"))
      (node (ref "5V1") (pin "4") (pinfunction "4_4") (pintype "passive"))
      (node (ref "5V1") (pin "5") (pinfunction "5_5") (pintype "passive"))
      (node (ref "5V1") (pin "6") (pinfunction "6_6") (pintype "passive"))
      (node (ref "5V1") (pin "7") (pinfunction "7_7") (pintype "passive"))
      (node (ref "5V1") (pin "8") (pinfunction "8_8") (pintype "passive"))
      (node (ref "5V1") (pin "9") (pinfunction "9_9") (pintype "passive"))
      (node (ref "5VC-2") (pin "-") (pinfunction "-_-") (pintype "passive"))
      (node (ref "5VC1") (pin "-") (pinfunction "-_-") (pintype "passive"))
      (node (ref "ATMEGA328P") (pin "22") (pinfunction "22_22") (pintype "passive"))
      (node (ref "ATMEGA328P") (pin "8") (pinfunction "8_8") (pintype "passive"))
      (node (ref "C1") (pin "1") (pinfunction "1_1") (pintype "passive"))
      (node (ref "C2") (pin "2") (pinfunction "2_2") (pintype "passive"))
      (node (ref "LED-R3") (pin "1") (pinfunction "1_1") (pintype "passive"))
      (node (ref "LED-R4") (pin "1") (pinfunction "1_1") (pintype "passive"))
      (node (ref "OUT") (pin "10") (pinfunction "KL_10") (pintype "passive"))
      (node (ref "OUT") (pin "2") (pinfunction "KL_2") (pintype "passive"))
      (node (ref "OUT") (pin "4") (pinfunction "KL_4") (pintype "passive"))
      (node (ref "OUT") (pin "6") (pinfunction "KL_6") (pintype "passive"))
      (node (ref "OUT") (pin "8") (pinfunction "KL_8") (pintype "passive"))
      (node (ref "PAD1") (pin "1") (pinfunction "P_1") (pintype "passive"))
      (node (ref "PAD4") (pin "1") (pinfunction "P_1") (pintype "passive"))
      (node (ref "PROGRAMMER") (pin "11") (pinfunction "11_11") (pintype "passive"))
      (node (ref "PROGRAMMER") (pin "12") (pinfunction "12_12") (pintype "passive"))
      (node (ref "QBP") (pin "1") (pinfunction "E_1") (pintype "passive"))
      (node (ref "QBR") (pin "1") (pinfunction "E_1") (pintype "passive"))
      (node (ref "QBZ") (pin "1") (pinfunction "E_1") (pintype "passive"))
      (node (ref "QCN") (pin "1") (pinfunction "E_1") (pintype "passive"))
      (node (ref "QREV") (pin "1") (pinfunction "E_1") (pintype "passive"))
      (node (ref "QRT") (pin "1") (pinfunction "E_1") (pintype "passive"))
      (node (ref "QTS") (pin "1") (pinfunction "E_1") (pintype "passive"))
      (node (ref "R-A0") (pin "2") (pinfunction "2_2") (pintype "passive"))
      (node (ref "R-A1") (pin "2") (pinfunction "2_2") (pintype "passive"))
      (node (ref "R-A2") (pin "2") (pinfunction "2_2") (pintype "passive"))
      (node (ref "R-A3") (pin "2") (pinfunction "2_2") (pintype "passive"))
      (node (ref "R-A4") (pin "2") (pinfunction "2_2") (pintype "passive"))
      (node (ref "R-A5") (pin "2") (pinfunction "2_2") (pintype "passive"))
      (node (ref "TVS-12V") (pin "2") (pinfunction "2_2") (pintype "passive"))
      (node (ref "TVS-12V1") (pin "2") (pinfunction "2_2") (pintype "passive"))
      (node (ref "TVS-5V") (pin "1") (pinfunction "1_1") (pintype "passive"))
      (node (ref "TVS-AR") (pin "1") (pinfunction "1_1") (pintype "passive"))
    )
    (net (code "36") (name "Net-(12-V-SUPPLYA-KL)") (class "Default")
      (node (ref "12-V-SUPPLY") (pin "1") (pinfunction "KL_1") (pintype "passive"))
      (node (ref "FUSE-A") (pin "2A") (pinfunction "2A_2A") (pintype "passive"))
      (node (ref "FUSE-A1") (pin "2") (pinfunction "2_2") (pintype "passive"))
      (node (ref "TVS-12V") (pin "1") (pinfunction "1_1") (pintype "passive"))
    )
    (net (code "37") (name "Net-(BPC-KL)") (class "Default")
      (node (ref "BP") (pin "3") (pinfunction "KL_3") (pintype "passive"))
      (node (ref "K-BP") (pin "O") (pinfunction "O_O") (pintype "passive"))
    )
    (net (code "38") (name "Net-(OK-BP-A)") (class "Default")
      (node (ref "OK-BP") (pin "1") (pinfunction "A_1") (pintype "passive"))
      (node (ref "R-BP") (pin "1") (pinfunction "1_1") (pintype "passive"))
    )
    (net (code "39") (name "Net-(OK-BP-C)") (class "Default")
      (node (ref "LED-BP") (pin "A") (pinfunction "A_A") (pintype "passive"))
      (node (ref "OK-BP") (pin "2") (pinfunction "C_2") (pintype "passive"))
    )
    (net (code "40") (name "Net-(OK-BP-COL)") (class "Default")
      (node (ref "D-BP") (pin "A") (pinfunction "A_A") (pintype "passive"))
      (node (ref "K-BP") (pin "2") (pinfunction "2_2") (pintype "passive"))
      (node (ref "OK-BP") (pin "4") (pinfunction "COL_4") (pintype "passive"))
      (node (ref "QBP") (pin "3") (pinfunction "C_3") (pintype "passive"))
    )
    (net (code "41") (name "Net-(OK-BP-EMIT)") (class "Default")
      (node (ref "OK-BP") (pin "3") (pinfunction "EMIT_3") (pintype "passive"))
      (node (ref "R-BPT") (pin "2") (pinfunction "2_2") (pintype "passive"))
    )
    (net (code "42") (name "Net-(OK-BR-A)") (class "Default")
      (node (ref "OK-BR") (pin "1") (pinfunction "A_1") (pintype "passive"))
      (node (ref "R-BR") (pin "1") (pinfunction "1_1") (pintype "passive"))
    )
    (net (code "43") (name "Net-(OK-BR-C)") (class "Default")
      (node (ref "LED-BR") (pin "A") (pinfunction "A_A") (pintype "passive"))
      (node (ref "OK-BR") (pin "2") (pinfunction "C_2") (pintype "passive"))
    )
    (net (code "44") (name "Net-(OK-BR-COL)") (class "Default")
      (node (ref "D-BR") (pin "A") (pinfunction "A_A") (pintype "passive"))
      (node (ref "K-BR") (pin "2") (pinfunction "2_2") (pintype "passive"))
      (node (ref "OK-BR") (pin "4") (pinfunction "COL_4") (pintype "passive"))
      (node (ref "QBR") (pin "3") (pinfunction "C_3") (pintype "passive"))
    )
    (net (code "45") (name "Net-(OK-BR-EMIT)") (class "Default")
      (node (ref "OK-BR") (pin "3") (pinfunction "EMIT_3") (pintype "passive"))
      (node (ref "R-BRT") (pin "2") (pinfunction "2_2") (pintype "passive"))
    )
    (net (code "46") (name "Net-(OK-BZ-A)") (class "Default")
      (node (ref "OK-BZ") (pin "1") (pinfunction "A_1") (pintype "passive"))
      (node (ref "R-BZ") (pin "1") (pinfunction "1_1") (pintype "passive"))
    )
    (net (code "47") (name "Net-(OK-BZ-C)") (class "Default")
      (node (ref "LED-BZ") (pin "A") (pinfunction "A_A") (pintype "passive"))
      (node (ref "OK-BZ") (pin "2") (pinfunction "C_2") (pintype "passive"))
    )
    (net (code "48") (name "Net-(OK-BZ-COL)") (class "Default")
      (node (ref "D-BZ") (pin "A") (pinfunction "A_A") (pintype "passive"))
      (node (ref "K-BZ") (pin "2") (pinfunction "2_2") (pintype "passive"))
      (node (ref "OK-BZ") (pin "4") (pinfunction "COL_4") (pintype "passive"))
      (node (ref "QBZ") (pin "3") (pinfunction "C_3") (pintype "passive"))
    )
    (net (code "49") (name "Net-(OK-BZ-EMIT)") (class "Default")
      (node (ref "OK-BZ") (pin "3") (pinfunction "EMIT_3") (pintype "passive"))
      (node (ref "R-BZT") (pin "2") (pinfunction "2_2") (pintype "passive"))
    )
    (net (code "50") (name "Net-(OK-CN-A)") (class "Default")
      (node (ref "OK-CN") (pin "1") (pinfunction "A_1") (pintype "passive"))
      (node (ref "R-CN") (pin "1") (pinfunction "1_1") (pintype "passive"))
    )
    (net (code "51") (name "Net-(OK-CN-C)") (class "Default")
      (node (ref "LED-CN") (pin "A") (pinfunction "A_A") (pintype "passive"))
      (node (ref "OK-CN") (pin "2") (pinfunction "C_2") (pintype "passive"))
    )
    (net (code "52") (name "Net-(OK-CN-COL)") (class "Default")
      (node (ref "D-CN") (pin "A") (pinfunction "A_A") (pintype "passive"))
      (node (ref "K-CN") (pin "2") (pinfunction "2_2") (pintype "passive"))
      (node (ref "OK-CN") (pin "4") (pinfunction "COL_4") (pintype "passive"))
      (node (ref "QCN") (pin "3") (pinfunction "C_3") (pintype "passive"))
    )
    (net (code "53") (name "Net-(OK-CN-EMIT)") (class "Default")
      (node (ref "OK-CN") (pin "3") (pinfunction "EMIT_3") (pintype "passive"))
      (node (ref "R-CNT") (pin "2") (pinfunction "2_2") (pintype "passive"))
    )
    (net (code "54") (name "Net-(OK-RD-A)") (class "Default")
      (node (ref "OK-RD") (pin "1") (pinfunction "A_1") (pintype "passive"))
      (node (ref "R-BP1") (pin "1") (pinfunction "1_1") (pintype "passive"))
    )
    (net (code "55") (name "Net-(OK-RD-C)") (class "Default")
      (node (ref "LED-BP1") (pin "A") (pinfunction "A_A") (pintype "passive"))
      (node (ref "OK-RD") (pin "2") (pinfunction "C_2") (pintype "passive"))
    )
    (net (code "56") (name "Net-(OK-RD-COL)") (class "Default")
      (node (ref "D-BP1") (pin "A") (pinfunction "A_A") (pintype "passive"))
      (node (ref "K-BP1") (pin "2") (pinfunction "2_2") (pintype "passive"))
      (node (ref "OK-RD") (pin "4") (pinfunction "COL_4") (pintype "passive"))
      (node (ref "QRT") (pin "3") (pinfunction "C_3") (pintype "passive"))
    )
    (net (code "57") (name "Net-(OK-RD-EMIT)") (class "Default")
      (node (ref "OK-RD") (pin "3") (pinfunction "EMIT_3") (pintype "passive"))
      (node (ref "R-RBP1T") (pin "2") (pinfunction "2_2") (pintype "passive"))
    )
    (net (code "58") (name "Net-(OK-RV-A)") (class "Default")
      (node (ref "OK-RV") (pin "1") (pinfunction "A_1") (pintype "passive"))
      (node (ref "R-REV") (pin "1") (pinfunction "1_1") (pintype "passive"))
    )
    (net (code "59") (name "Net-(OK-RV-C)") (class "Default")
      (node (ref "LED-RV") (pin "A") (pinfunction "A_A") (pintype "passive"))
      (node (ref "OK-RV") (pin "2") (pinfunction "C_2") (pintype "passive"))
    )
    (net (code "60") (name "Net-(OK-RV-COL)") (class "Default")
      (node (ref "D-REV") (pin "A") (pinfunction "A_A") (pintype "passive"))
      (node (ref "K-REV") (pin "2") (pinfunction "2_2") (pintype "passive"))
      (node (ref "OK-RV") (pin "4") (pinfunction "COL_4") (pintype "passive"))
      (node (ref "QREV") (pin "3") (pinfunction "C_3") (pintype "passive"))
    )
    (net (code "61") (name "Net-(OK-RV-EMIT)") (class "Default")
      (node (ref "OK-RV") (pin "3") (pinfunction "EMIT_3") (pintype "passive"))
      (node (ref "R-REVT") (pin "2") (pinfunction "2_2") (pintype "passive"))
    )
    (net (code "62") (name "Net-(OK-TS-A)") (class "Default")
      (node (ref "OK-TS") (pin "1") (pinfunction "A_1") (pintype "passive"))
      (node (ref "R-TS") (pin "1") (pinfunction "1_1") (pintype "passive"))
    )
    (net (code "63") (name "Net-(OK-TS-C)") (class "Default")
      (node (ref "LED-TS") (pin "A") (pinfunction "A_A") (pintype "passive"))
      (node (ref "OK-TS") (pin "2") (pinfunction "C_2") (pintype "passive"))
    )
    (net (code "64") (name "Net-(OK-TS-COL)") (class "Default")
      (node (ref "D-TS") (pin "A") (pinfunction "A_A") (pintype "passive"))
      (node (ref "K-TS") (pin "2") (pinfunction "2_2") (pintype "passive"))
      (node (ref "OK-TS") (pin "4") (pinfunction "COL_4") (pintype "passive"))
      (node (ref "QTS") (pin "3") (pinfunction "C_3") (pintype "passive"))
    )
    (net (code "65") (name "Net-(OK-TS-EMIT)") (class "Default")
      (node (ref "OK-TS") (pin "3") (pinfunction "EMIT_3") (pintype "passive"))
      (node (ref "R-TST") (pin "2") (pinfunction "2_2") (pintype "passive"))
    )
    (net (code "66") (name "Net-(PAD3-P)") (class "Default")
      (node (ref "FUSE-5V") (pin "2A") (pinfunction "2A_2A") (pintype "passive"))
      (node (ref "FUSE-5V1") (pin "1") (pinfunction "1_1") (pintype "passive"))
      (node (ref "PAD3") (pin "1") (pinfunction "P_1") (pintype "passive"))
      (node (ref "TVS-5V") (pin "2") (pinfunction "2_2") (pintype "passive"))
    )
    (net (code "67") (name "Net-(PROGRAMMER-Pad10)") (class "Default")
      (node (ref "PROGRAMMER") (pin "10") (pinfunction "10_10") (pintype "passive"))
      (node (ref "PROGRAMMER") (pin "9") (pinfunction "9_9") (pintype "passive"))
    )
    (net (code "68") (name "Net-(QBP-B)") (class "Default")
      (node (ref "QBP") (pin "2") (pinfunction "B_2") (pintype "passive"))
      (node (ref "R-BPT") (pin "1") (pinfunction "1_1") (pintype "passive"))
    )
    (net (code "69") (name "Net-(QBR-B)") (class "Default")
      (node (ref "QBR") (pin "2") (pinfunction "B_2") (pintype "passive"))
      (node (ref "R-BRT") (pin "1") (pinfunction "1_1") (pintype "passive"))
    )
    (net (code "70") (name "Net-(QBZ-B)") (class "Default")
      (node (ref "QBZ") (pin "2") (pinfunction "B_2") (pintype "passive"))
      (node (ref "R-BZT") (pin "1") (pinfunction "1_1") (pintype "passive"))
    )
    (net (code "71") (name "Net-(QCN-B)") (class "Default")
      (node (ref "QCN") (pin "2") (pinfunction "B_2") (pintype "passive"))
      (node (ref "R-CNT") (pin "1") (pinfunction "1_1") (pintype "passive"))
    )
    (net (code "72") (name "Net-(QREV-B)") (class "Default")
      (node (ref "QREV") (pin "2") (pinfunction "B_2") (pintype "passive"))
      (node (ref "R-REVT") (pin "1") (pinfunction "1_1") (pintype "passive"))
    )
    (net (code "73") (name "Net-(QRT-B)") (class "Default")
      (node (ref "QRT") (pin "2") (pinfunction "B_2") (pintype "passive"))
      (node (ref "R-RBP1T") (pin "1") (pinfunction "1_1") (pintype "passive"))
    )
    (net (code "74") (name "Net-(QTS-B)") (class "Default")
      (node (ref "QTS") (pin "2") (pinfunction "B_2") (pintype "passive"))
      (node (ref "R-TST") (pin "1") (pinfunction "1_1") (pintype "passive"))
    )
    (net (code "75") (name "unconnected-(ATMEGA328P-Pad21)") (class "Default")
      (node (ref "ATMEGA328P") (pin "21") (pinfunction "21_21") (pintype "passive"))
    )
    (net (code "76") (name "unconnected-(BP1A-KL-Pad1)") (class "Default")
      (node (ref "BP1") (pin "1") (pinfunction "KL_1") (pintype "passive"))
    )
    (net (code "77") (name "unconnected-(BP1C-KL-Pad3)") (class "Default")
      (node (ref "BP1") (pin "3") (pinfunction "KL_3") (pintype "passive"))
    )
    (net (code "78") (name "unconnected-(BR-12C-KL-Pad3)") (class "Default")
      (node (ref "BR-12") (pin "3") (pinfunction "KL_3") (pintype "passive"))
    )
    (net (code "79") (name "unconnected-(BZC-KL-Pad3)") (class "Default")
      (node (ref "BZ") (pin "3") (pinfunction "KL_3") (pintype "passive"))
    )
    (net (code "80") (name "unconnected-(CNC-KL-Pad3)") (class "Default")
      (node (ref "CN") (pin "3") (pinfunction "KL_3") (pintype "passive"))
    )
    (net (code "81") (name "unconnected-(FUSE-5V-Pad1B)") (class "Default")
      (node (ref "FUSE-5V") (pin "1B") (pinfunction "1B_1B") (pintype "passive"))
    )
    (net (code "82") (name "unconnected-(FUSE-5V-Pad2B)") (class "Default")
      (node (ref "FUSE-5V") (pin "2B") (pinfunction "2B_2B") (pintype "passive"))
    )
    (net (code "83") (name "unconnected-(FUSE-A-Pad1B)") (class "Default")
      (node (ref "FUSE-A") (pin "1B") (pinfunction "1B_1B") (pintype "passive"))
    )
    (net (code "84") (name "unconnected-(FUSE-A-Pad2B)") (class "Default")
      (node (ref "FUSE-A") (pin "2B") (pinfunction "2B_2B") (pintype "passive"))
    )
    (net (code "85") (name "unconnected-(K-BP1-PadO)") (class "Default")
      (node (ref "K-BP1") (pin "O") (pinfunction "O_O") (pintype "passive"))
    )
    (net (code "86") (name "unconnected-(K-BP1-PadS)") (class "Default")
      (node (ref "K-BP1") (pin "S") (pinfunction "S_S") (pintype "passive"))
    )
    (net (code "87") (name "unconnected-(K-BR-PadO)") (class "Default")
      (node (ref "K-BR") (pin "O") (pinfunction "O_O") (pintype "passive"))
    )
    (net (code "88") (name "unconnected-(K-BZ-PadO)") (class "Default")
      (node (ref "K-BZ") (pin "O") (pinfunction "O_O") (pintype "passive"))
    )
    (net (code "89") (name "unconnected-(K-CN-PadO)") (class "Default")
      (node (ref "K-CN") (pin "O") (pinfunction "O_O") (pintype "passive"))
    )
    (net (code "90") (name "unconnected-(K-REV-PadO)") (class "Default")
      (node (ref "K-REV") (pin "O") (pinfunction "O_O") (pintype "passive"))
    )
    (net (code "91") (name "unconnected-(K-TS-PadO)") (class "Default")
      (node (ref "K-TS") (pin "O") (pinfunction "O_O") (pintype "passive"))
    )
    (net (code "92") (name "unconnected-(RVC-KL-Pad3)") (class "Default")
      (node (ref "RV") (pin "3") (pinfunction "KL_3") (pintype "passive"))
    )
  )
)
